# Relay_Board.net
KiCad netlist of a schematic drawn in EAGLE
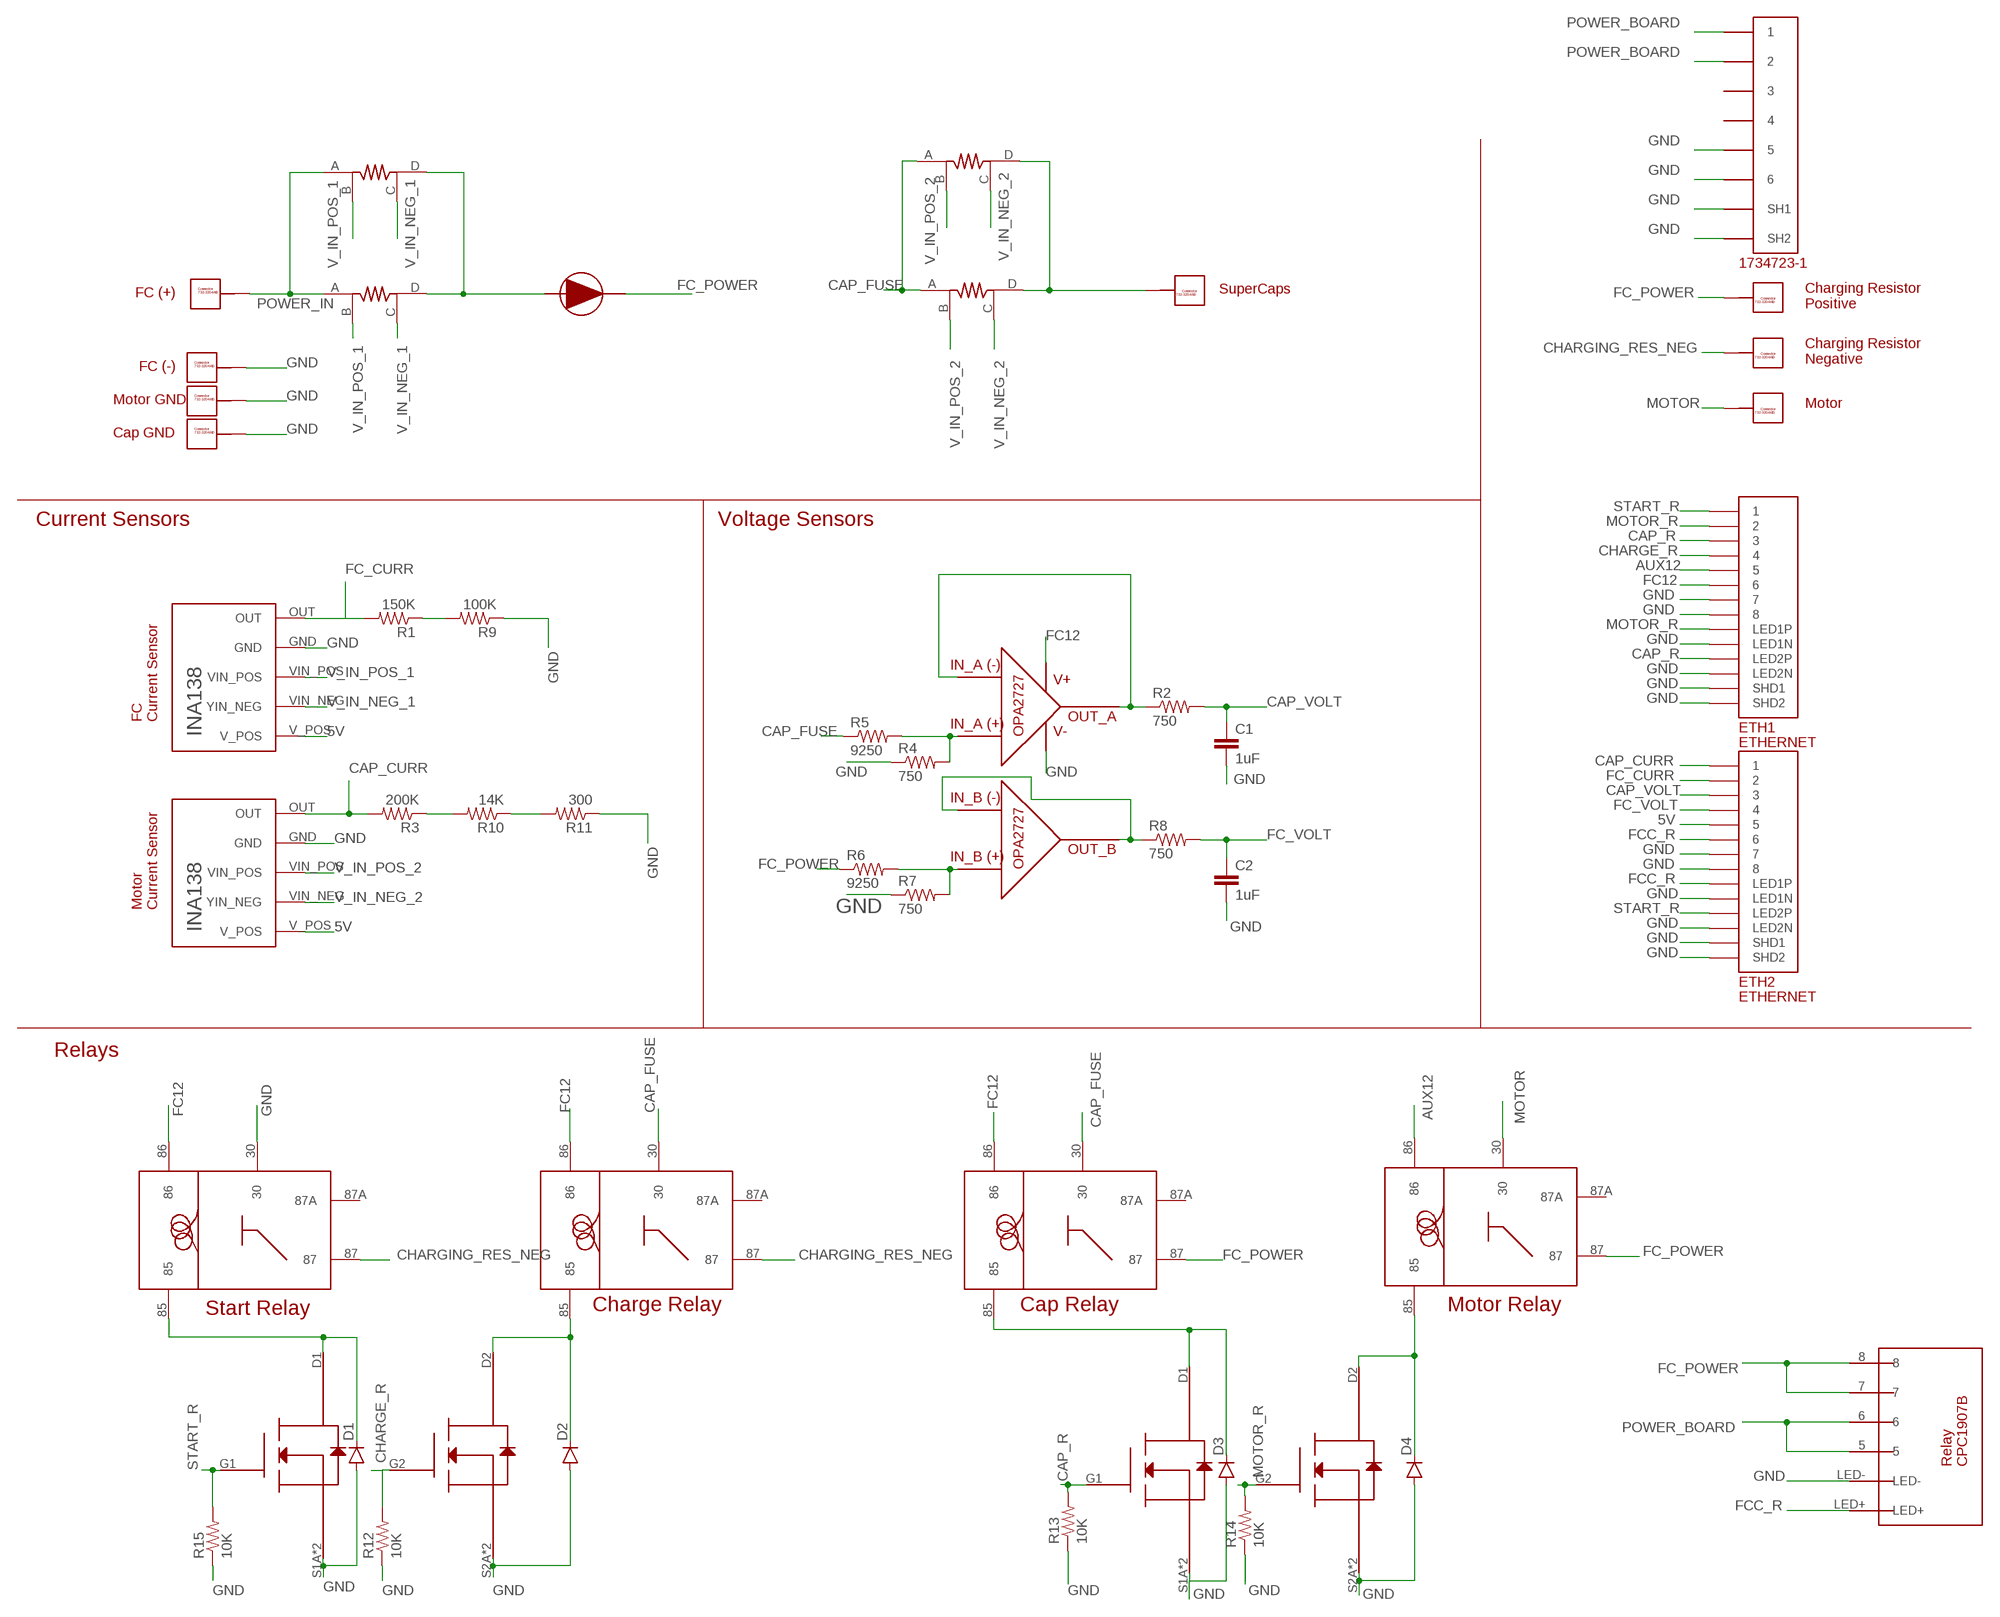
[diagram p0: schematic, sheet 1]

(export (version "E")
  (design (tool "Eeschema 10.0.6"))
  (components
    (comp (ref "C1")
      (value "1uF")
      (footprint "eagle-import:0402-CAP")
      (libsource (lib "eagle-import") (part "CAP0402-CAP"))
    )
    (comp (ref "C2")
      (value "1uF")
      (footprint "eagle-import:0402-CAP")
      (libsource (lib "eagle-import") (part "CAP0402-CAP"))
    )
    (comp (ref "D1")
      (value "DIODESOD123")
      (footprint "eagle-import:SOD-123")
      (libsource (lib "eagle-import") (part "DIODESOD123"))
    )
    (comp (ref "D2")
      (value "DIODESOD123")
      (footprint "eagle-import:SOD-123")
      (libsource (lib "eagle-import") (part "DIODESOD123"))
    )
    (comp (ref "D3")
      (value "DIODESOD123")
      (footprint "eagle-import:SOD-123")
      (libsource (lib "eagle-import") (part "DIODESOD123"))
    )
    (comp (ref "D4")
      (value "DIODESOD123")
      (footprint "eagle-import:SOD-123")
      (libsource (lib "eagle-import") (part "DIODESOD123"))
    )
    (comp (ref "ETH1")
      (value "ETHERNET")
      (footprint "eagle-import:A122645-ND")
      (libsource (lib "eagle-import") (part "ETHERNET"))
    )
    (comp (ref "ETH2")
      (value "ETHERNET")
      (footprint "eagle-import:A122645-ND")
      (libsource (lib "eagle-import") (part "ETHERNET"))
    )
    (comp (ref "R1")
      (value "150K")
      (footprint "eagle-import:1206")
      (libsource (lib "eagle-import") (part "RESISTOR1206"))
    )
    (comp (ref "R2")
      (value "750")
      (footprint "eagle-import:1206")
      (libsource (lib "eagle-import") (part "RESISTOR1206"))
    )
    (comp (ref "R3")
      (value "200K")
      (footprint "eagle-import:1206")
      (libsource (lib "eagle-import") (part "RESISTOR1206"))
    )
    (comp (ref "R4")
      (value "750")
      (footprint "eagle-import:1206")
      (libsource (lib "eagle-import") (part "RESISTOR1206"))
    )
    (comp (ref "R5")
      (value "9250")
      (footprint "eagle-import:1206")
      (libsource (lib "eagle-import") (part "RESISTOR1206"))
    )
    (comp (ref "R6")
      (value "9250")
      (footprint "eagle-import:1206")
      (libsource (lib "eagle-import") (part "RESISTOR1206"))
    )
    (comp (ref "R7")
      (value "750")
      (footprint "eagle-import:1206")
      (libsource (lib "eagle-import") (part "RESISTOR1206"))
    )
    (comp (ref "R8")
      (value "750")
      (footprint "eagle-import:1206")
      (libsource (lib "eagle-import") (part "RESISTOR1206"))
    )
    (comp (ref "R9")
      (value "100K")
      (footprint "eagle-import:1206")
      (libsource (lib "eagle-import") (part "RESISTOR1206"))
    )
    (comp (ref "R10")
      (value "14K")
      (footprint "eagle-import:1206")
      (libsource (lib "eagle-import") (part "RESISTOR1206"))
    )
    (comp (ref "R11")
      (value "300")
      (footprint "eagle-import:1206")
      (libsource (lib "eagle-import") (part "RESISTOR1206"))
    )
    (comp (ref "R12")
      (value "10K")
      (footprint "eagle-import:0603-RES")
      (libsource (lib "eagle-import") (part "RESISTOR0603-RES"))
    )
    (comp (ref "R13")
      (value "10K")
      (footprint "eagle-import:0603-RES")
      (libsource (lib "eagle-import") (part "RESISTOR0603-RES"))
    )
    (comp (ref "R14")
      (value "10K")
      (footprint "eagle-import:0603-RES")
      (libsource (lib "eagle-import") (part "RESISTOR0603-RES"))
    )
    (comp (ref "R15")
      (value "10K")
      (footprint "eagle-import:0603-RES")
      (libsource (lib "eagle-import") (part "RESISTOR0603-RES"))
    )
    (comp (ref "U$1")
      (value "732-3204-ND_CONNECTOR")
      (footprint "eagle-import:732-3204-ND")
      (libsource (lib "eagle-import") (part "732-3204-ND_CONNECTOR"))
    )
    (comp (ref "U$2")
      (value "732-3204-ND_CONNECTOR")
      (footprint "eagle-import:732-3204-ND")
      (libsource (lib "eagle-import") (part "732-3204-ND_CONNECTOR"))
    )
    (comp (ref "U$3")
      (value "TI_INA138")
      (footprint "eagle-import:TI_INA138")
      (libsource (lib "eagle-import") (part "TI_INA138"))
    )
    (comp (ref "U$4")
      (value "SHUNT_RESISTOR_CSM3637")
      (footprint "eagle-import:CSM3637")
      (libsource (lib "eagle-import") (part "SHUNT_RESISTOR_CSM3637"))
    )
    (comp (ref "U$5")
      (value "DIODE-APT60S20BG")
      (footprint "eagle-import:DIODE-APT60S20BG")
      (libsource (lib "eagle-import") (part "DIODE-APT60S20BG"))
    )
    (comp (ref "U$6")
      (value "SHUNT_RESISTOR_CSM3637")
      (footprint "eagle-import:CSM3637")
      (libsource (lib "eagle-import") (part "SHUNT_RESISTOR_CSM3637"))
    )
    (comp (ref "U$7")
      (value "TI_INA138")
      (footprint "eagle-import:TI_INA138")
      (libsource (lib "eagle-import") (part "TI_INA138"))
    )
    (comp (ref "U$8")
      (value "VCF4-1000")
      (footprint "eagle-import:VCF4-1000")
      (libsource (lib "eagle-import") (part "VCF4-1000"))
    )
    (comp (ref "U$9")
      (value "SI6926ADQ-T1-E3CT-ND_MOSFET")
      (footprint "eagle-import:SI6926ADQ-T1-E3CT-ND_MOSFET")
      (libsource (lib "eagle-import") (part "SI6926ADQ-T1-E3CT-ND_MOSFET"))
    )
    (comp (ref "U$10")
      (value "732-3204-ND_CONNECTOR")
      (footprint "eagle-import:732-3204-ND")
      (libsource (lib "eagle-import") (part "732-3204-ND_CONNECTOR"))
    )
    (comp (ref "U$11")
      (value "VCF4-1000")
      (footprint "eagle-import:VCF4-1000")
      (libsource (lib "eagle-import") (part "VCF4-1000"))
    )
    (comp (ref "U$12")
      (value "SHUNT_RESISTOR_CSM3637")
      (footprint "eagle-import:CSM3637")
      (libsource (lib "eagle-import") (part "SHUNT_RESISTOR_CSM3637"))
    )
    (comp (ref "U$13")
      (value "732-3204-ND_CONNECTOR")
      (footprint "eagle-import:732-3204-ND")
      (libsource (lib "eagle-import") (part "732-3204-ND_CONNECTOR"))
    )
    (comp (ref "U$14")
      (value "732-3204-ND_CONNECTOR")
      (footprint "eagle-import:732-3204-ND")
      (libsource (lib "eagle-import") (part "732-3204-ND_CONNECTOR"))
    )
    (comp (ref "U$15")
      (value "VCF4-1000")
      (footprint "eagle-import:VCF4-1000")
      (libsource (lib "eagle-import") (part "VCF4-1000"))
    )
    (comp (ref "U$17")
      (value "OP-AMP_OPA2727AIDR")
      (footprint "eagle-import:OP-AMP_OPA2727AIDR")
      (libsource (lib "eagle-import") (part "OP-AMP_OPA2727AIDR"))
    )
    (comp (ref "U$18")
      (value "VCF4-1000")
      (footprint "eagle-import:VCF4-1000")
      (libsource (lib "eagle-import") (part "VCF4-1000"))
    )
    (comp (ref "U$19")
      (value "5555140-6")
      (footprint "eagle-import:1734723-1_RJ11")
      (libsource (lib "eagle-import") (part "5555140-6"))
    )
    (comp (ref "U$20")
      (value "732-3204-ND_CONNECTOR")
      (footprint "eagle-import:732-3204-ND")
      (libsource (lib "eagle-import") (part "732-3204-ND_CONNECTOR"))
    )
    (comp (ref "U$21")
      (value "SHUNT_RESISTOR_CSM3637")
      (footprint "eagle-import:CSM3637")
      (libsource (lib "eagle-import") (part "SHUNT_RESISTOR_CSM3637"))
    )
    (comp (ref "U$22")
      (value "RELAY-CPC1907B")
      (footprint "eagle-import:RELAY-CPC1907B")
      (libsource (lib "eagle-import") (part "RELAY-CPC1907B"))
    )
    (comp (ref "U$23")
      (value "732-3204-ND_CONNECTOR")
      (footprint "eagle-import:732-3204-ND")
      (libsource (lib "eagle-import") (part "732-3204-ND_CONNECTOR"))
    )
    (comp (ref "U$24")
      (value "732-3204-ND_CONNECTOR")
      (footprint "eagle-import:732-3204-ND")
      (libsource (lib "eagle-import") (part "732-3204-ND_CONNECTOR"))
    )
    (comp (ref "U$25")
      (value "SI6926ADQ-T1-E3CT-ND_MOSFET")
      (footprint "eagle-import:SI6926ADQ-T1-E3CT-ND_MOSFET")
      (libsource (lib "eagle-import") (part "SI6926ADQ-T1-E3CT-ND_MOSFET"))
    )
  )
  (nets
    (net (code "1") (name "/5V") (class "Default")
      (node (ref "ETH2") (pin "P$5") (pinfunction "5_P$5") (pintype "bidirectional"))
      (node (ref "U$3") (pin "V_POS") (pinfunction "V_POS_V_POS") (pintype "bidirectional"))
      (node (ref "U$7") (pin "V_POS") (pinfunction "V_POS_V_POS") (pintype "bidirectional"))
    )
    (net (code "2") (name "/AUX12") (class "Default")
      (node (ref "ETH1") (pin "P$5") (pinfunction "5_P$5") (pintype "bidirectional"))
      (node (ref "U$18") (pin "86") (pinfunction "86_86") (pintype "bidirectional"))
    )
    (net (code "3") (name "/CAP_CURR") (class "Default")
      (node (ref "ETH2") (pin "P$1") (pinfunction "1_P$1") (pintype "bidirectional"))
      (node (ref "R3") (pin "2") (pinfunction "2_2") (pintype "passive"))
      (node (ref "U$3") (pin "OUT") (pinfunction "OUT_OUT") (pintype "bidirectional"))
    )
    (net (code "4") (name "/CAP_FUSE") (class "Default")
      (node (ref "R5") (pin "1") (pinfunction "1_1") (pintype "passive"))
      (node (ref "U$11") (pin "30") (pinfunction "30_30") (pintype "bidirectional"))
      (node (ref "U$12") (pin "A") (pinfunction "A_A") (pintype "bidirectional"))
      (node (ref "U$21") (pin "A") (pinfunction "A_A") (pintype "bidirectional"))
      (node (ref "U$8") (pin "30") (pinfunction "30_30") (pintype "bidirectional"))
    )
    (net (code "5") (name "/CAP_R") (class "Default")
      (node (ref "ETH1") (pin "P$12") (pinfunction "LED2P_P$12") (pintype "bidirectional"))
      (node (ref "ETH1") (pin "P$3") (pinfunction "3_P$3") (pintype "bidirectional"))
      (node (ref "R13") (pin "2") (pinfunction "2_2") (pintype "passive"))
      (node (ref "U$9") (pin "G1") (pinfunction "G1_G1") (pintype "bidirectional"))
    )
    (net (code "6") (name "/CAP_VOLT") (class "Default")
      (node (ref "C1") (pin "1") (pinfunction "1_1") (pintype "passive"))
      (node (ref "ETH2") (pin "P$3") (pinfunction "3_P$3") (pintype "bidirectional"))
      (node (ref "R2") (pin "2") (pinfunction "2_2") (pintype "passive"))
    )
    (net (code "7") (name "/CHARGE_R") (class "Default")
      (node (ref "ETH1") (pin "P$4") (pinfunction "4_P$4") (pintype "bidirectional"))
      (node (ref "R12") (pin "2") (pinfunction "2_2") (pintype "passive"))
      (node (ref "U$25") (pin "G2") (pinfunction "G2_G2") (pintype "bidirectional"))
    )
    (net (code "8") (name "/CHARGING_RES_NEG") (class "Default")
      (node (ref "U$11") (pin "87") (pinfunction "87_87") (pintype "bidirectional"))
      (node (ref "U$14") (pin "P$1") (pinfunction "P$1_P$1") (pintype "bidirectional"))
      (node (ref "U$14") (pin "P$10") (pinfunction "P$1_P$10") (pintype "bidirectional"))
      (node (ref "U$14") (pin "P$2") (pinfunction "P$1_P$2") (pintype "bidirectional"))
      (node (ref "U$14") (pin "P$3") (pinfunction "P$1_P$3") (pintype "bidirectional"))
      (node (ref "U$14") (pin "P$4") (pinfunction "P$1_P$4") (pintype "bidirectional"))
      (node (ref "U$14") (pin "P$5") (pinfunction "P$1_P$5") (pintype "bidirectional"))
      (node (ref "U$14") (pin "P$6") (pinfunction "P$1_P$6") (pintype "bidirectional"))
      (node (ref "U$14") (pin "P$7") (pinfunction "P$1_P$7") (pintype "bidirectional"))
      (node (ref "U$14") (pin "P$8") (pinfunction "P$1_P$8") (pintype "bidirectional"))
      (node (ref "U$14") (pin "P$9") (pinfunction "P$1_P$9") (pintype "bidirectional"))
      (node (ref "U$15") (pin "87") (pinfunction "87_87") (pintype "bidirectional"))
    )
    (net (code "9") (name "/FC12") (class "Default")
      (node (ref "ETH1") (pin "P$6") (pinfunction "6_P$6") (pintype "bidirectional"))
      (node (ref "U$11") (pin "86") (pinfunction "86_86") (pintype "bidirectional"))
      (node (ref "U$15") (pin "86") (pinfunction "86_86") (pintype "bidirectional"))
      (node (ref "U$17") (pin "V+") (pinfunction "V+_V+") (pintype "bidirectional"))
      (node (ref "U$8") (pin "86") (pinfunction "86_86") (pintype "bidirectional"))
    )
    (net (code "10") (name "/FCC_R") (class "Default")
      (node (ref "ETH2") (pin "P$10") (pinfunction "LED1P_P$10") (pintype "bidirectional"))
      (node (ref "ETH2") (pin "P$6") (pinfunction "6_P$6") (pintype "bidirectional"))
      (node (ref "U$22") (pin "LED+") (pinfunction "LED+_LED+") (pintype "bidirectional"))
    )
    (net (code "11") (name "/FC_CURR") (class "Default")
      (node (ref "ETH2") (pin "P$2") (pinfunction "2_P$2") (pintype "bidirectional"))
      (node (ref "R1") (pin "2") (pinfunction "2_2") (pintype "passive"))
      (node (ref "U$7") (pin "OUT") (pinfunction "OUT_OUT") (pintype "bidirectional"))
    )
    (net (code "12") (name "/FC_POWER") (class "Default")
      (node (ref "R6") (pin "1") (pinfunction "1_1") (pintype "passive"))
      (node (ref "U$13") (pin "P$1") (pinfunction "P$1_P$1") (pintype "bidirectional"))
      (node (ref "U$13") (pin "P$10") (pinfunction "P$1_P$10") (pintype "bidirectional"))
      (node (ref "U$13") (pin "P$2") (pinfunction "P$1_P$2") (pintype "bidirectional"))
      (node (ref "U$13") (pin "P$3") (pinfunction "P$1_P$3") (pintype "bidirectional"))
      (node (ref "U$13") (pin "P$4") (pinfunction "P$1_P$4") (pintype "bidirectional"))
      (node (ref "U$13") (pin "P$5") (pinfunction "P$1_P$5") (pintype "bidirectional"))
      (node (ref "U$13") (pin "P$6") (pinfunction "P$1_P$6") (pintype "bidirectional"))
      (node (ref "U$13") (pin "P$7") (pinfunction "P$1_P$7") (pintype "bidirectional"))
      (node (ref "U$13") (pin "P$8") (pinfunction "P$1_P$8") (pintype "bidirectional"))
      (node (ref "U$13") (pin "P$9") (pinfunction "P$1_P$9") (pintype "bidirectional"))
      (node (ref "U$18") (pin "87") (pinfunction "87_87") (pintype "bidirectional"))
      (node (ref "U$22") (pin "7") (pinfunction "7_7") (pintype "bidirectional"))
      (node (ref "U$22") (pin "8") (pinfunction "8_8") (pintype "bidirectional"))
      (node (ref "U$5") (pin "CATHODE") (pinfunction "CATHODE_CATHODE") (pintype "output"))
      (node (ref "U$8") (pin "87") (pinfunction "87_87") (pintype "bidirectional"))
    )
    (net (code "13") (name "/FC_VOLT") (class "Default")
      (node (ref "C2") (pin "1") (pinfunction "1_1") (pintype "passive"))
      (node (ref "ETH2") (pin "P$4") (pinfunction "4_P$4") (pintype "bidirectional"))
      (node (ref "R8") (pin "2") (pinfunction "2_2") (pintype "passive"))
    )
    (net (code "14") (name "/GND") (class "Default")
      (node (ref "C1") (pin "2") (pinfunction "2_2") (pintype "passive"))
      (node (ref "C2") (pin "2") (pinfunction "2_2") (pintype "passive"))
      (node (ref "D1") (pin "A") (pinfunction "A_A") (pintype "passive"))
      (node (ref "D2") (pin "A") (pinfunction "A_A") (pintype "passive"))
      (node (ref "D3") (pin "A") (pinfunction "A_A") (pintype "passive"))
      (node (ref "D4") (pin "A") (pinfunction "A_A") (pintype "passive"))
      (node (ref "ETH1") (pin "P$11") (pinfunction "LED2N_P$11") (pintype "bidirectional"))
      (node (ref "ETH1") (pin "P$13") (pinfunction "SHD1_P$13") (pintype "bidirectional"))
      (node (ref "ETH1") (pin "P$14") (pinfunction "SHD2_P$14") (pintype "bidirectional"))
      (node (ref "ETH1") (pin "P$7") (pinfunction "7_P$7") (pintype "bidirectional"))
      (node (ref "ETH1") (pin "P$8") (pinfunction "8_P$8") (pintype "bidirectional"))
      (node (ref "ETH1") (pin "P$9") (pinfunction "LED1N_P$9") (pintype "bidirectional"))
      (node (ref "ETH2") (pin "P$11") (pinfunction "LED2N_P$11") (pintype "bidirectional"))
      (node (ref "ETH2") (pin "P$13") (pinfunction "SHD1_P$13") (pintype "bidirectional"))
      (node (ref "ETH2") (pin "P$14") (pinfunction "SHD2_P$14") (pintype "bidirectional"))
      (node (ref "ETH2") (pin "P$7") (pinfunction "7_P$7") (pintype "bidirectional"))
      (node (ref "ETH2") (pin "P$8") (pinfunction "8_P$8") (pintype "bidirectional"))
      (node (ref "ETH2") (pin "P$9") (pinfunction "LED1N_P$9") (pintype "bidirectional"))
      (node (ref "R11") (pin "1") (pinfunction "1_1") (pintype "passive"))
      (node (ref "R12") (pin "1") (pinfunction "1_1") (pintype "passive"))
      (node (ref "R13") (pin "1") (pinfunction "1_1") (pintype "passive"))
      (node (ref "R14") (pin "1") (pinfunction "1_1") (pintype "passive"))
      (node (ref "R15") (pin "1") (pinfunction "1_1") (pintype "passive"))
      (node (ref "R4") (pin "1") (pinfunction "1_1") (pintype "passive"))
      (node (ref "R7") (pin "1") (pinfunction "1_1") (pintype "passive"))
      (node (ref "R9") (pin "1") (pinfunction "1_1") (pintype "passive"))
      (node (ref "U$15") (pin "30") (pinfunction "30_30") (pintype "bidirectional"))
      (node (ref "U$17") (pin "V-") (pinfunction "V-_V-") (pintype "bidirectional"))
      (node (ref "U$19") (pin "5") (pinfunction "5_5") (pintype "bidirectional"))
      (node (ref "U$19") (pin "6") (pinfunction "6_6") (pintype "bidirectional"))
      (node (ref "U$19") (pin "SH1") (pinfunction "SH1_SH1") (pintype "bidirectional"))
      (node (ref "U$19") (pin "SH2") (pinfunction "SH2_SH2") (pintype "bidirectional"))
      (node (ref "U$2") (pin "P$1") (pinfunction "P$1_P$1") (pintype "bidirectional"))
      (node (ref "U$2") (pin "P$10") (pinfunction "P$1_P$10") (pintype "bidirectional"))
      (node (ref "U$2") (pin "P$2") (pinfunction "P$1_P$2") (pintype "bidirectional"))
      (node (ref "U$2") (pin "P$3") (pinfunction "P$1_P$3") (pintype "bidirectional"))
      (node (ref "U$2") (pin "P$4") (pinfunction "P$1_P$4") (pintype "bidirectional"))
      (node (ref "U$2") (pin "P$5") (pinfunction "P$1_P$5") (pintype "bidirectional"))
      (node (ref "U$2") (pin "P$6") (pinfunction "P$1_P$6") (pintype "bidirectional"))
      (node (ref "U$2") (pin "P$7") (pinfunction "P$1_P$7") (pintype "bidirectional"))
      (node (ref "U$2") (pin "P$8") (pinfunction "P$1_P$8") (pintype "bidirectional"))
      (node (ref "U$2") (pin "P$9") (pinfunction "P$1_P$9") (pintype "bidirectional"))
      (node (ref "U$22") (pin "LED-") (pinfunction "LED-_LED-") (pintype "bidirectional"))
      (node (ref "U$23") (pin "P$1") (pinfunction "P$1_P$1") (pintype "bidirectional"))
      (node (ref "U$23") (pin "P$10") (pinfunction "P$1_P$10") (pintype "bidirectional"))
      (node (ref "U$23") (pin "P$2") (pinfunction "P$1_P$2") (pintype "bidirectional"))
      (node (ref "U$23") (pin "P$3") (pinfunction "P$1_P$3") (pintype "bidirectional"))
      (node (ref "U$23") (pin "P$4") (pinfunction "P$1_P$4") (pintype "bidirectional"))
      (node (ref "U$23") (pin "P$5") (pinfunction "P$1_P$5") (pintype "bidirectional"))
      (node (ref "U$23") (pin "P$6") (pinfunction "P$1_P$6") (pintype "bidirectional"))
      (node (ref "U$23") (pin "P$7") (pinfunction "P$1_P$7") (pintype "bidirectional"))
      (node (ref "U$23") (pin "P$8") (pinfunction "P$1_P$8") (pintype "bidirectional"))
      (node (ref "U$23") (pin "P$9") (pinfunction "P$1_P$9") (pintype "bidirectional"))
      (node (ref "U$24") (pin "P$1") (pinfunction "P$1_P$1") (pintype "bidirectional"))
      (node (ref "U$24") (pin "P$10") (pinfunction "P$1_P$10") (pintype "bidirectional"))
      (node (ref "U$24") (pin "P$2") (pinfunction "P$1_P$2") (pintype "bidirectional"))
      (node (ref "U$24") (pin "P$3") (pinfunction "P$1_P$3") (pintype "bidirectional"))
      (node (ref "U$24") (pin "P$4") (pinfunction "P$1_P$4") (pintype "bidirectional"))
      (node (ref "U$24") (pin "P$5") (pinfunction "P$1_P$5") (pintype "bidirectional"))
      (node (ref "U$24") (pin "P$6") (pinfunction "P$1_P$6") (pintype "bidirectional"))
      (node (ref "U$24") (pin "P$7") (pinfunction "P$1_P$7") (pintype "bidirectional"))
      (node (ref "U$24") (pin "P$8") (pinfunction "P$1_P$8") (pintype "bidirectional"))
      (node (ref "U$24") (pin "P$9") (pinfunction "P$1_P$9") (pintype "bidirectional"))
      (node (ref "U$25") (pin "S1A") (pinfunction "S1_S1A") (pintype "bidirectional"))
      (node (ref "U$25") (pin "S1B") (pinfunction "S1_S1B") (pintype "bidirectional"))
      (node (ref "U$25") (pin "S2A") (pinfunction "S2_S2A") (pintype "bidirectional"))
      (node (ref "U$25") (pin "S2B") (pinfunction "S2_S2B") (pintype "bidirectional"))
      (node (ref "U$3") (pin "GND") (pinfunction "GND_GND") (pintype "bidirectional"))
      (node (ref "U$7") (pin "GND") (pinfunction "GND_GND") (pintype "bidirectional"))
      (node (ref "U$9") (pin "S1A") (pinfunction "S1_S1A") (pintype "bidirectional"))
      (node (ref "U$9") (pin "S1B") (pinfunction "S1_S1B") (pintype "bidirectional"))
      (node (ref "U$9") (pin "S2A") (pinfunction "S2_S2A") (pintype "bidirectional"))
      (node (ref "U$9") (pin "S2B") (pinfunction "S2_S2B") (pintype "bidirectional"))
    )
    (net (code "15") (name "/MOTOR") (class "Default")
      (node (ref "U$18") (pin "30") (pinfunction "30_30") (pintype "bidirectional"))
      (node (ref "U$20") (pin "P$1") (pinfunction "P$1_P$1") (pintype "bidirectional"))
      (node (ref "U$20") (pin "P$10") (pinfunction "P$1_P$10") (pintype "bidirectional"))
      (node (ref "U$20") (pin "P$2") (pinfunction "P$1_P$2") (pintype "bidirectional"))
      (node (ref "U$20") (pin "P$3") (pinfunction "P$1_P$3") (pintype "bidirectional"))
      (node (ref "U$20") (pin "P$4") (pinfunction "P$1_P$4") (pintype "bidirectional"))
      (node (ref "U$20") (pin "P$5") (pinfunction "P$1_P$5") (pintype "bidirectional"))
      (node (ref "U$20") (pin "P$6") (pinfunction "P$1_P$6") (pintype "bidirectional"))
      (node (ref "U$20") (pin "P$7") (pinfunction "P$1_P$7") (pintype "bidirectional"))
      (node (ref "U$20") (pin "P$8") (pinfunction "P$1_P$8") (pintype "bidirectional"))
      (node (ref "U$20") (pin "P$9") (pinfunction "P$1_P$9") (pintype "bidirectional"))
    )
    (net (code "16") (name "/MOTOR_R") (class "Default")
      (node (ref "ETH1") (pin "P$10") (pinfunction "LED1P_P$10") (pintype "bidirectional"))
      (node (ref "ETH1") (pin "P$2") (pinfunction "2_P$2") (pintype "bidirectional"))
      (node (ref "R14") (pin "2") (pinfunction "2_2") (pintype "passive"))
      (node (ref "U$9") (pin "G2") (pinfunction "G2_G2") (pintype "bidirectional"))
    )
    (net (code "17") (name "/POWER_BOARD") (class "Default")
      (node (ref "U$19") (pin "1") (pinfunction "1_1") (pintype "bidirectional"))
      (node (ref "U$19") (pin "2") (pinfunction "2_2") (pintype "bidirectional"))
      (node (ref "U$22") (pin "5") (pinfunction "5_5") (pintype "bidirectional"))
      (node (ref "U$22") (pin "6") (pinfunction "6_6") (pintype "bidirectional"))
    )
    (net (code "18") (name "/POWER_IN") (class "Default")
      (node (ref "U$1") (pin "P$1") (pinfunction "P$1_P$1") (pintype "bidirectional"))
      (node (ref "U$1") (pin "P$10") (pinfunction "P$1_P$10") (pintype "bidirectional"))
      (node (ref "U$1") (pin "P$2") (pinfunction "P$1_P$2") (pintype "bidirectional"))
      (node (ref "U$1") (pin "P$3") (pinfunction "P$1_P$3") (pintype "bidirectional"))
      (node (ref "U$1") (pin "P$4") (pinfunction "P$1_P$4") (pintype "bidirectional"))
      (node (ref "U$1") (pin "P$5") (pinfunction "P$1_P$5") (pintype "bidirectional"))
      (node (ref "U$1") (pin "P$6") (pinfunction "P$1_P$6") (pintype "bidirectional"))
      (node (ref "U$1") (pin "P$7") (pinfunction "P$1_P$7") (pintype "bidirectional"))
      (node (ref "U$1") (pin "P$8") (pinfunction "P$1_P$8") (pintype "bidirectional"))
      (node (ref "U$1") (pin "P$9") (pinfunction "P$1_P$9") (pintype "bidirectional"))
      (node (ref "U$4") (pin "A") (pinfunction "A_A") (pintype "bidirectional"))
      (node (ref "U$6") (pin "A") (pinfunction "A_A") (pintype "bidirectional"))
    )
    (net (code "19") (name "/START_R") (class "Default")
      (node (ref "ETH1") (pin "P$1") (pinfunction "1_P$1") (pintype "bidirectional"))
      (node (ref "ETH2") (pin "P$12") (pinfunction "LED2P_P$12") (pintype "bidirectional"))
      (node (ref "R15") (pin "2") (pinfunction "2_2") (pintype "passive"))
      (node (ref "U$25") (pin "G1") (pinfunction "G1_G1") (pintype "bidirectional"))
    )
    (net (code "20") (name "/V_IN_NEG_1") (class "Default")
      (node (ref "U$4") (pin "C") (pinfunction "C_C") (pintype "bidirectional"))
      (node (ref "U$6") (pin "C") (pinfunction "C_C") (pintype "bidirectional"))
      (node (ref "U$7") (pin "VIN_NEG") (pinfunction "YIN_NEG_VIN_NEG") (pintype "bidirectional"))
    )
    (net (code "21") (name "/V_IN_NEG_2") (class "Default")
      (node (ref "U$12") (pin "C") (pinfunction "C_C") (pintype "bidirectional"))
      (node (ref "U$21") (pin "C") (pinfunction "C_C") (pintype "bidirectional"))
      (node (ref "U$3") (pin "VIN_NEG") (pinfunction "YIN_NEG_VIN_NEG") (pintype "bidirectional"))
    )
    (net (code "22") (name "/V_IN_POS_1") (class "Default")
      (node (ref "U$4") (pin "B") (pinfunction "B_B") (pintype "bidirectional"))
      (node (ref "U$6") (pin "B") (pinfunction "B_B") (pintype "bidirectional"))
      (node (ref "U$7") (pin "VIN_POS") (pinfunction "VIN_POS_VIN_POS") (pintype "bidirectional"))
    )
    (net (code "23") (name "/V_IN_POS_2") (class "Default")
      (node (ref "U$12") (pin "B") (pinfunction "B_B") (pintype "bidirectional"))
      (node (ref "U$21") (pin "B") (pinfunction "B_B") (pintype "bidirectional"))
      (node (ref "U$3") (pin "VIN_POS") (pinfunction "VIN_POS_VIN_POS") (pintype "bidirectional"))
    )
    (net (code "24") (name "Net-(D1-PadC)") (class "Default")
      (node (ref "D1") (pin "C") (pinfunction "C_C") (pintype "passive"))
      (node (ref "U$15") (pin "85") (pinfunction "85_85") (pintype "bidirectional"))
      (node (ref "U$25") (pin "D1") (pinfunction "D1_D1") (pintype "bidirectional"))
    )
    (net (code "25") (name "Net-(D2-PadC)") (class "Default")
      (node (ref "D2") (pin "C") (pinfunction "C_C") (pintype "passive"))
      (node (ref "U$11") (pin "85") (pinfunction "85_85") (pintype "bidirectional"))
      (node (ref "U$25") (pin "D2") (pinfunction "D2_D2") (pintype "bidirectional"))
    )
    (net (code "26") (name "Net-(D3-PadC)") (class "Default")
      (node (ref "D3") (pin "C") (pinfunction "C_C") (pintype "passive"))
      (node (ref "U$8") (pin "85") (pinfunction "85_85") (pintype "bidirectional"))
      (node (ref "U$9") (pin "D1") (pinfunction "D1_D1") (pintype "bidirectional"))
    )
    (net (code "27") (name "Net-(D4-PadC)") (class "Default")
      (node (ref "D4") (pin "C") (pinfunction "C_C") (pintype "passive"))
      (node (ref "U$18") (pin "85") (pinfunction "85_85") (pintype "bidirectional"))
      (node (ref "U$9") (pin "D2") (pinfunction "D2_D2") (pintype "bidirectional"))
    )
    (net (code "28") (name "Net-(R1-Pad1)") (class "Default")
      (node (ref "R1") (pin "1") (pinfunction "1_1") (pintype "passive"))
      (node (ref "R9") (pin "2") (pinfunction "2_2") (pintype "passive"))
    )
    (net (code "29") (name "Net-(R2-Pad1)") (class "Default")
      (node (ref "R2") (pin "1") (pinfunction "1_1") (pintype "passive"))
      (node (ref "U$17") (pin "IN_A-") (pinfunction "IN_A-_IN_A-") (pintype "bidirectional"))
      (node (ref "U$17") (pin "OUT_A") (pinfunction "OUT_A_OUT_A") (pintype "bidirectional"))
    )
    (net (code "30") (name "Net-(R4-Pad2)") (class "Default")
      (node (ref "R4") (pin "2") (pinfunction "2_2") (pintype "passive"))
      (node (ref "R5") (pin "2") (pinfunction "2_2") (pintype "passive"))
      (node (ref "U$17") (pin "IN_A+") (pinfunction "IN_A+_IN_A+") (pintype "bidirectional"))
    )
    (net (code "31") (name "Net-(R6-Pad2)") (class "Default")
      (node (ref "R6") (pin "2") (pinfunction "2_2") (pintype "passive"))
      (node (ref "R7") (pin "2") (pinfunction "2_2") (pintype "passive"))
      (node (ref "U$17") (pin "IN_B+") (pinfunction "IN_B+_IN_B+") (pintype "bidirectional"))
    )
    (net (code "32") (name "Net-(R8-Pad1)") (class "Default")
      (node (ref "R8") (pin "1") (pinfunction "1_1") (pintype "passive"))
      (node (ref "U$17") (pin "IN_B-") (pinfunction "IN_B-_IN_B-") (pintype "bidirectional"))
      (node (ref "U$17") (pin "OUT_B") (pinfunction "OUT_B_OUT_B") (pintype "bidirectional"))
    )
    (net (code "33") (name "Net-(R10-Pad1)") (class "Default")
      (node (ref "R10") (pin "1") (pinfunction "1_1") (pintype "passive"))
      (node (ref "R11") (pin "2") (pinfunction "2_2") (pintype "passive"))
    )
    (net (code "34") (name "Net-(R10-Pad2)") (class "Default")
      (node (ref "R10") (pin "2") (pinfunction "2_2") (pintype "passive"))
      (node (ref "R3") (pin "1") (pinfunction "1_1") (pintype "passive"))
    )
    (net (code "35") (name "Net-(U$4-PadD)") (class "Default")
      (node (ref "U$4") (pin "D") (pinfunction "D_D") (pintype "bidirectional"))
      (node (ref "U$5") (pin "ANODE") (pinfunction "ANODE_ANODE") (pintype "input"))
      (node (ref "U$6") (pin "D") (pinfunction "D_D") (pintype "bidirectional"))
    )
    (net (code "36") (name "Net-(U$10-P$1-PadP$10)") (class "Default")
      (node (ref "U$10") (pin "P$1") (pinfunction "P$1_P$1") (pintype "bidirectional"))
      (node (ref "U$10") (pin "P$10") (pinfunction "P$1_P$10") (pintype "bidirectional"))
      (node (ref "U$10") (pin "P$2") (pinfunction "P$1_P$2") (pintype "bidirectional"))
      (node (ref "U$10") (pin "P$3") (pinfunction "P$1_P$3") (pintype "bidirectional"))
      (node (ref "U$10") (pin "P$4") (pinfunction "P$1_P$4") (pintype "bidirectional"))
      (node (ref "U$10") (pin "P$5") (pinfunction "P$1_P$5") (pintype "bidirectional"))
      (node (ref "U$10") (pin "P$6") (pinfunction "P$1_P$6") (pintype "bidirectional"))
      (node (ref "U$10") (pin "P$7") (pinfunction "P$1_P$7") (pintype "bidirectional"))
      (node (ref "U$10") (pin "P$8") (pinfunction "P$1_P$8") (pintype "bidirectional"))
      (node (ref "U$10") (pin "P$9") (pinfunction "P$1_P$9") (pintype "bidirectional"))
      (node (ref "U$12") (pin "D") (pinfunction "D_D") (pintype "bidirectional"))
      (node (ref "U$21") (pin "D") (pinfunction "D_D") (pintype "bidirectional"))
    )
    (net (code "37") (name "unconnected-(U$8-Pad87A)") (class "Default")
      (node (ref "U$8") (pin "87A") (pinfunction "87A_87A") (pintype "bidirectional"))
    )
    (net (code "38") (name "unconnected-(U$11-Pad87A)") (class "Default")
      (node (ref "U$11") (pin "87A") (pinfunction "87A_87A") (pintype "bidirectional"))
    )
    (net (code "39") (name "unconnected-(U$15-Pad87A)") (class "Default")
      (node (ref "U$15") (pin "87A") (pinfunction "87A_87A") (pintype "bidirectional"))
    )
    (net (code "40") (name "unconnected-(U$18-Pad87A)") (class "Default")
      (node (ref "U$18") (pin "87A") (pinfunction "87A_87A") (pintype "bidirectional"))
    )
    (net (code "41") (name "unconnected-(U$19-Pad3)") (class "Default")
      (node (ref "U$19") (pin "3") (pinfunction "3_3") (pintype "bidirectional"))
    )
    (net (code "42") (name "unconnected-(U$19-Pad4)") (class "Default")
      (node (ref "U$19") (pin "4") (pinfunction "4_4") (pintype "bidirectional"))
    )
  )
)
